# SWR_Tandem_Match.net
KiCad netlist of a schematic drawn in Altium Designer
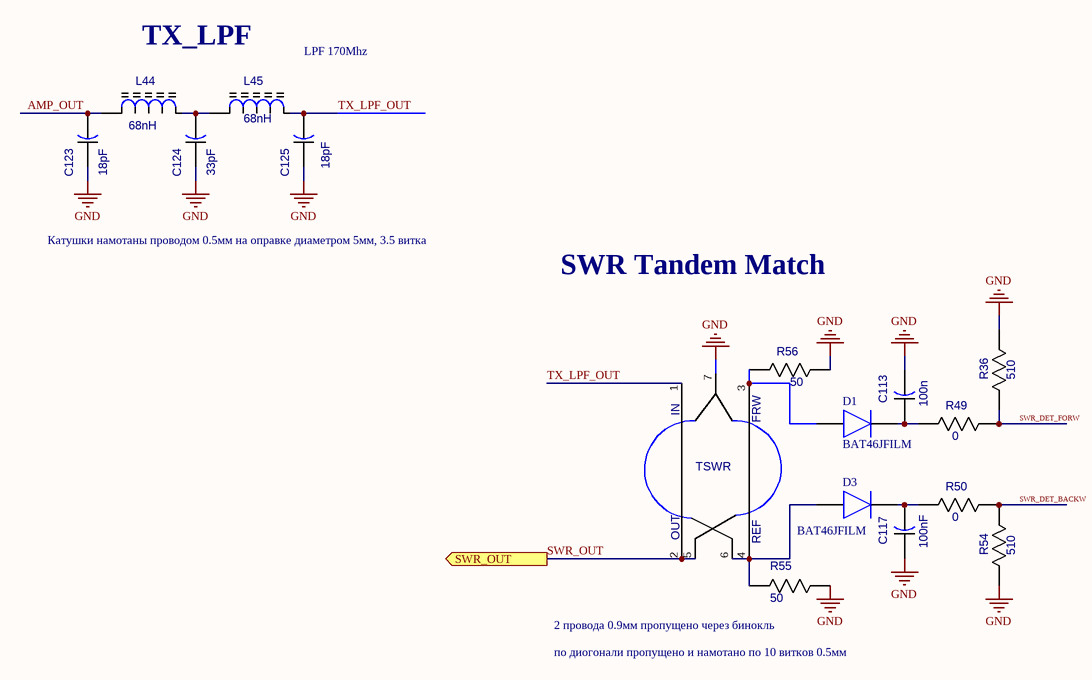
[diagram p0: SWR Tandem Match.SchDoc]

(export (version "E")
  (design (tool "Eeschema 10.0.6"))
  (components
    (comp (ref "C113")
      (value "100n")
      (footprint "CAP_0805")
      (description "CAP_0805")
      (libsource (lib "*") (part "CAP_0805"))
    )
    (comp (ref "C117")
      (value "100nF")
      (footprint "CAP_0805")
      (description "CAP_0805")
      (libsource (lib "*") (part "CAP_0805"))
    )
    (comp (ref "C123")
      (value "18pF")
      (footprint "CAP_1206")
      (description "CAP_1206")
      (libsource (lib "*") (part "CAP_1206"))
    )
    (comp (ref "C124")
      (value "33pF")
      (footprint "CAP_1206")
      (description "CAP_1206")
      (libsource (lib "*") (part "CAP_1206"))
    )
    (comp (ref "C125")
      (value "18pF")
      (footprint "CAP_1206")
      (description "CAP_1206")
      (libsource (lib "*") (part "CAP_1206"))
    )
    (comp (ref "D1")
      (value "BAT46JFILM")
      (footprint "SamacSys:SOD2513X117N")
      (description "Diode")
      (fields (field (name "MOUSER PART NUMBER") "511-BAT46JFILM") (field (name "RS PART NUMBER") "7146847P"))
      (libsource (lib "*") (part "BAT46JFILM"))
    )
    (comp (ref "D3")
      (value "BAT46JFILM")
      (footprint "SamacSys:SOD2513X117N")
      (description "Diode")
      (fields (field (name "MOUSER PART NUMBER") "511-BAT46JFILM") (field (name "RS PART NUMBER") "7146847P"))
      (libsource (lib "*") (part "BAT46JFILM"))
    )
    (comp (ref "L44")
      (value "68nH")
      (footprint "IND_FERRITE_CORE_1")
      (description "Inductor")
      (libsource (lib "*") (part "IND_FERRITE_CORE"))
    )
    (comp (ref "L45")
      (value "68nH")
      (footprint "IND_FERRITE_CORE_1")
      (description "Inductor")
      (libsource (lib "*") (part "IND_FERRITE_CORE"))
    )
    (comp (ref "R36")
      (value "510")
      (footprint "RES_0805")
      (description "RES_0805")
      (libsource (lib "*") (part "RES_0805"))
    )
    (comp (ref "R49")
      (value "0")
      (footprint "RES_0805")
      (description "RES_0805")
      (libsource (lib "*") (part "RES_0805"))
    )
    (comp (ref "R50")
      (value "0")
      (footprint "RES_0805")
      (description "RES_0805")
      (libsource (lib "*") (part "RES_0805"))
    )
    (comp (ref "R54")
      (value "510")
      (footprint "RES_0805")
      (description "RES_0805")
      (libsource (lib "*") (part "RES_0805"))
    )
    (comp (ref "R55")
      (value "50")
      (footprint "RES_1206")
      (description "RES_1206")
      (libsource (lib "*") (part "RES_1206"))
    )
    (comp (ref "R56")
      (value "50")
      (footprint "RES_1206")
      (description "RES_1206")
      (libsource (lib "*") (part "RES_1206"))
    )
    (comp (ref "TSWR")
      (value "SWR_TANDEM_MATCH")
      (footprint "SWR_TANDEM_MATCH")
      (libsource (lib "*") (part "SWR_TANDEM_MATCH"))
    )
  )
  (nets
    (net (code "1") (name "/AMP_OUT") (class "Default")
      (node (ref "C123") (pin "2") (pinfunction "2_2") (pintype "passive"))
      (node (ref "L44") (pin "1") (pinfunction "A_1") (pintype "passive"))
    )
    (net (code "2") (name "/SWR_DET_BACKW") (class "Default")
      (node (ref "R50") (pin "2") (pinfunction "2_2") (pintype "passive"))
      (node (ref "R54") (pin "2") (pinfunction "2_2") (pintype "passive"))
    )
    (net (code "3") (name "/SWR_DET_FORW") (class "Default")
      (node (ref "R36") (pin "1") (pinfunction "1_1") (pintype "passive"))
      (node (ref "R49") (pin "2") (pinfunction "2_2") (pintype "passive"))
    )
    (net (code "4") (name "/SWR_OUT") (class "Default")
      (node (ref "TSWR") (pin "2") (pinfunction "2_2") (pintype "passive"))
      (node (ref "TSWR") (pin "5") (pinfunction "5_5") (pintype "passive"))
    )
    (net (code "5") (name "/TX_LPF_OUT") (class "Default")
      (node (ref "C125") (pin "2") (pinfunction "2_2") (pintype "passive"))
      (node (ref "L45") (pin "2") (pinfunction "B_2") (pintype "passive"))
      (node (ref "TSWR") (pin "1") (pinfunction "1_1") (pintype "passive"))
    )
    (net (code "6") (name "GND") (class "Default")
      (node (ref "C113") (pin "2") (pinfunction "2_2") (pintype "passive"))
      (node (ref "C117") (pin "1") (pinfunction "1_1") (pintype "passive"))
      (node (ref "C123") (pin "1") (pinfunction "1_1") (pintype "passive"))
      (node (ref "C124") (pin "1") (pinfunction "1_1") (pintype "passive"))
      (node (ref "C125") (pin "1") (pinfunction "1_1") (pintype "passive"))
      (node (ref "R36") (pin "2") (pinfunction "2_2") (pintype "passive"))
      (node (ref "R54") (pin "1") (pinfunction "1_1") (pintype "passive"))
      (node (ref "R55") (pin "2") (pinfunction "2_2") (pintype "passive"))
      (node (ref "R56") (pin "2") (pinfunction "2_2") (pintype "passive"))
      (node (ref "TSWR") (pin "7") (pinfunction "7_7") (pintype "passive"))
    )
    (net (code "7") (name "Net-(D1-A)") (class "Default")
      (node (ref "D1") (pin "2") (pinfunction "A_2") (pintype "passive"))
      (node (ref "R56") (pin "1") (pinfunction "1_1") (pintype "passive"))
      (node (ref "TSWR") (pin "3") (pinfunction "3_3") (pintype "passive"))
    )
    (net (code "8") (name "Net-(D1-K)") (class "Default")
      (node (ref "C113") (pin "1") (pinfunction "1_1") (pintype "passive"))
      (node (ref "D1") (pin "1") (pinfunction "K_1") (pintype "passive"))
      (node (ref "R49") (pin "1") (pinfunction "1_1") (pintype "passive"))
    )
    (net (code "9") (name "Net-(D3-A)") (class "Default")
      (node (ref "D3") (pin "2") (pinfunction "A_2") (pintype "passive"))
      (node (ref "R55") (pin "1") (pinfunction "1_1") (pintype "passive"))
      (node (ref "TSWR") (pin "4") (pinfunction "4_4") (pintype "passive"))
      (node (ref "TSWR") (pin "6") (pinfunction "6_6") (pintype "passive"))
    )
    (net (code "10") (name "Net-(D3-K)") (class "Default")
      (node (ref "C117") (pin "2") (pinfunction "2_2") (pintype "passive"))
      (node (ref "D3") (pin "1") (pinfunction "K_1") (pintype "passive"))
      (node (ref "R50") (pin "1") (pinfunction "1_1") (pintype "passive"))
    )
    (net (code "11") (name "Net-(L44-B)") (class "Default")
      (node (ref "C124") (pin "2") (pinfunction "2_2") (pintype "passive"))
      (node (ref "L44") (pin "2") (pinfunction "B_2") (pintype "passive"))
      (node (ref "L45") (pin "1") (pinfunction "A_1") (pintype "passive"))
    )
  )
)
